# clusterwink_rev0.net
KiCad netlist of a schematic drawn in Altium Designer
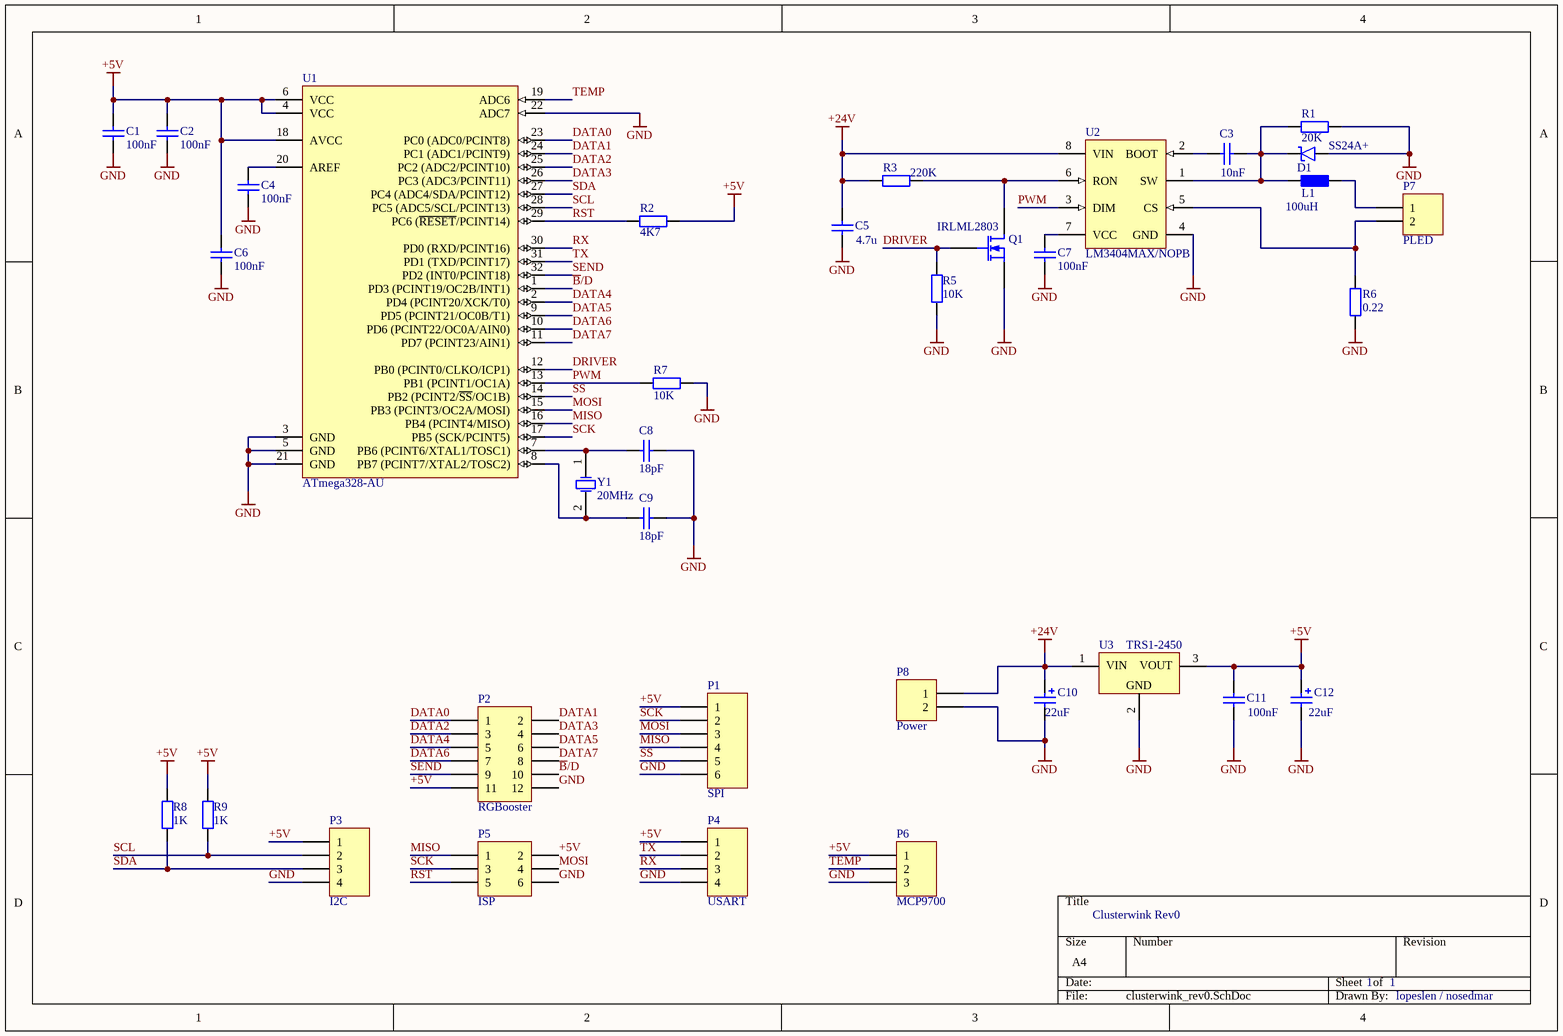
[diagram p0: clusterwink_rev0.SchDoc]

(export (version "E")
  (design (tool "Eeschema 10.0.6"))
  (components
    (comp (ref "C1")
      (value "100nF")
      (footprint "6-0805_M")
      (description "Capacitor")
      (fields (field (name "Comment") "Cap") (field (name "PUBLISHER") "Altium Limited"))
      (libsource (lib "Miscellaneous Devices") (part "Cap"))
    )
    (comp (ref "C2")
      (value "100nF")
      (footprint "6-0805_M")
      (description "Capacitor")
      (fields (field (name "Comment") "Cap") (field (name "PUBLISHER") "Altium Limited"))
      (libsource (lib "Miscellaneous Devices") (part "Cap"))
    )
    (comp (ref "C3")
      (value "10nF")
      (footprint "6-0805_M")
      (description "Capacitor")
      (fields (field (name "Comment") "Cap") (field (name "PUBLISHER") "Altium Limited"))
      (libsource (lib "Miscellaneous Devices") (part "Cap"))
    )
    (comp (ref "C4")
      (value "100nF")
      (footprint "6-0805_M")
      (description "Capacitor")
      (fields (field (name "Comment") "Cap") (field (name "PUBLISHER") "Altium Limited"))
      (libsource (lib "Miscellaneous Devices") (part "Cap"))
    )
    (comp (ref "C5")
      (value "4.7u")
      (footprint "C1206")
      (description "Capacitor")
      (fields (field (name "Comment") "Cap") (field (name "PUBLISHER") "Altium Limited"))
      (libsource (lib "Miscellaneous Devices") (part "Cap"))
    )
    (comp (ref "C6")
      (value "100nF")
      (footprint "6-0805_M")
      (description "Capacitor")
      (fields (field (name "Comment") "Cap") (field (name "PUBLISHER") "Altium Limited"))
      (libsource (lib "Miscellaneous Devices") (part "Cap"))
    )
    (comp (ref "C7")
      (value "100nF")
      (footprint "6-0805_M")
      (description "Capacitor")
      (fields (field (name "Comment") "Cap") (field (name "PUBLISHER") "Altium Limited"))
      (libsource (lib "Miscellaneous Devices") (part "Cap"))
    )
    (comp (ref "C8")
      (value "18pF")
      (footprint "6-0805_M")
      (description "Capacitor")
      (fields (field (name "Comment") "Cap") (field (name "PUBLISHER") "Altium Limited"))
      (libsource (lib "Miscellaneous Devices") (part "Cap"))
    )
    (comp (ref "C9")
      (value "18pF")
      (footprint "6-0805_M")
      (description "Capacitor")
      (fields (field (name "Comment") "Cap") (field (name "PUBLISHER") "Altium Limited"))
      (libsource (lib "Miscellaneous Devices") (part "Cap"))
    )
    (comp (ref "C10")
      (value "22uF")
      (footprint "EEEFK1H220P")
      (description "Polarized Capacitor (Axial)")
      (fields (field (name "Comment") "Cap Pol2") (field (name "PUBLISHER") "Altium Limited"))
      (libsource (lib "Miscellaneous Devices") (part "Cap Pol2"))
    )
    (comp (ref "C11")
      (value "100nF")
      (footprint "6-0805_M")
      (description "Capacitor")
      (fields (field (name "Comment") "Cap") (field (name "PUBLISHER") "Altium Limited"))
      (libsource (lib "Miscellaneous Devices") (part "Cap"))
    )
    (comp (ref "C12")
      (value "22uF")
      (footprint "EEEFK1H220P")
      (description "Polarized Capacitor (Axial)")
      (fields (field (name "Comment") "Cap Pol2") (field (name "PUBLISHER") "Altium Limited"))
      (libsource (lib "Miscellaneous Devices") (part "Cap Pol2"))
    )
    (comp (ref "D1") (value "SS24A+") (footprint "DO-214") (libsource (lib "etp") (part "Schottky")))
    (comp (ref "L1")
      (value "100uH")
      (footprint "ELLCTP")
      (fields (field (name "Comment") "Ind"))
      (libsource (lib "etp") (part "Inductor"))
    )
    (comp (ref "P1")
      (value "SPI")
      (footprint "HDR1X6")
      (description "Header, 6-Pin")
      (fields (field (name "PUBLISHER") "Altium Limited"))
      (libsource (lib "Miscellaneous Connectors") (part "Header 6"))
    )
    (comp (ref "P2")
      (value "RGBooster")
      (footprint "Klemme_90deg_inv")
      (description "Header, 6-Pin, Dual row")
      (fields (field (name "PUBLISHER") "Altium Limited"))
      (libsource (lib "Miscellaneous Connectors") (part "Header 6X2"))
    )
    (comp (ref "P3")
      (value "I2C")
      (footprint "HDR1X4")
      (description "Header, 4-Pin")
      (fields (field (name "PUBLISHER") "Altium Limited"))
      (libsource (lib "Miscellaneous Connectors") (part "Header 4"))
    )
    (comp (ref "P4")
      (value "USART")
      (footprint "HDR1X4")
      (description "Header, 4-Pin")
      (fields (field (name "PUBLISHER") "Altium Limited"))
      (libsource (lib "Miscellaneous Connectors") (part "Header 4"))
    )
    (comp (ref "P5")
      (value "ISP")
      (footprint "AVR_ISP")
      (description "Header, 3-Pin, Dual row")
      (fields (field (name "PUBLISHER") "Altium Limited"))
      (libsource (lib "Miscellaneous Connectors") (part "Header 3X2"))
    )
    (comp (ref "P6")
      (value "MCP9700")
      (footprint "HDR1X3")
      (description "Header, 3-Pin")
      (fields (field (name "PUBLISHER") "Altium Limited"))
      (libsource (lib "Miscellaneous Connectors") (part "Header 3"))
    )
    (comp (ref "P7")
      (value "PLED")
      (footprint "HDR1X2")
      (description "Header, 2-Pin")
      (fields (field (name "PUBLISHER") "Altium Limited"))
      (libsource (lib "") (part "Header 2_1"))
    )
    (comp (ref "P8")
      (value "Power")
      (footprint "HDR1X2")
      (description "Header, 2-Pin")
      (fields (field (name "PUBLISHER") "Altium Limited"))
      (libsource (lib "Miscellaneous Connectors") (part "Header 2"))
    )
    (comp (ref "Q1")
      (value "IRLML2803")
      (footprint "SOT-23")
      (description "N-Channel MOSFET")
      (fields (field (name "PUBLISHER") "Altium Limited"))
      (libsource (lib "Miscellaneous Devices") (part "MOSFET-N"))
    )
    (comp (ref "R1")
      (value "20K")
      (footprint "6-0805_M")
      (description "Resistor")
      (fields (field (name "Comment") "Res2") (field (name "PUBLISHER") "Altium Limited"))
      (libsource (lib "") (part "Res2_2"))
    )
    (comp (ref "R2")
      (value "4K7")
      (footprint "6-0805_M")
      (description "Resistor")
      (fields (field (name "Comment") "Res2") (field (name "PUBLISHER") "Altium Limited"))
      (libsource (lib "") (part "Res2_2"))
    )
    (comp (ref "R3")
      (value "220K")
      (footprint "6-0805_M")
      (description "Resistor")
      (fields (field (name "Comment") "Res2") (field (name "PUBLISHER") "Altium Limited"))
      (libsource (lib "") (part "Res2_3"))
    )
    (comp (ref "R5")
      (value "10K")
      (footprint "6-0805_M")
      (description "Resistor")
      (fields (field (name "Comment") "Res2") (field (name "PUBLISHER") "Altium Limited"))
      (libsource (lib "Miscellaneous Devices") (part "Res2"))
    )
    (comp (ref "R6")
      (value "0.22")
      (footprint "C1206")
      (description "Resistor")
      (fields (field (name "Comment") "Res2") (field (name "PUBLISHER") "Altium Limited"))
      (libsource (lib "Miscellaneous Devices") (part "Res2"))
    )
    (comp (ref "R7")
      (value "10K")
      (footprint "6-0805_M")
      (description "Resistor")
      (fields (field (name "Comment") "Res2") (field (name "PUBLISHER") "Altium Limited"))
      (libsource (lib "") (part "Res2_2"))
    )
    (comp (ref "R8")
      (value "1K")
      (footprint "6-0805_M")
      (description "Resistor")
      (fields (field (name "Comment") "Res2") (field (name "PUBLISHER") "Altium Limited"))
      (libsource (lib "") (part "Res2_1"))
    )
    (comp (ref "R9")
      (value "1K")
      (footprint "6-0805_M")
      (description "Resistor")
      (fields (field (name "Comment") "Res2") (field (name "PUBLISHER") "Altium Limited"))
      (libsource (lib "") (part "Res2_1"))
    )
    (comp (ref "U1")
      (value "ATmega328-AU")
      (footprint "32A_N")
      (libsource (lib "Atmel Microcontroller megaAVR") (part "ATmega328-AU"))
    )
    (comp (ref "U2")
      (value "LM3404MAX/NOPB")
      (footprint "M08A_N")
      (description "1.0A Constant Current Buck Regulator for High Power LED Drivers, 8-pin Narrow SOIC, Pb-Free")
      (fields (field (name "MANUFACTURER") "National Semiconductor"))
      (libsource (lib "National Semiconductor MiscPower") (part "LM3404MAX/NOPB"))
    )
    (comp (ref "U3") (value "TRS1-2450") (footprint "TRS 1-2450") (libsource (lib "etp") (part "TSR1-2450")))
    (comp (ref "Y1")
      (value "20MHz")
      (footprint "CRYSTAL")
      (description "Crystal Oscillator")
      (fields (field (name "PUBLISHER") "Altium Limited"))
      (libsource (lib "Miscellaneous Devices") (part "XTAL"))
    )
  )
  (nets
    (net (code "1") (name "+5V") (class "Default")
      (node (ref "C1") (pin "2") (pinfunction "2_2") (pintype "passive"))
      (node (ref "C11") (pin "2") (pinfunction "2_2") (pintype "passive"))
      (node (ref "C12") (pin "1") (pinfunction "1_1") (pintype "passive"))
      (node (ref "C2") (pin "2") (pinfunction "2_2") (pintype "passive"))
      (node (ref "C6") (pin "2") (pinfunction "2_2") (pintype "passive"))
      (node (ref "P1") (pin "1") (pinfunction "1_1") (pintype "passive"))
      (node (ref "P2") (pin "11") (pinfunction "11_11") (pintype "passive"))
      (node (ref "P3") (pin "1") (pinfunction "1_1") (pintype "passive"))
      (node (ref "P4") (pin "1") (pinfunction "1_1") (pintype "passive"))
      (node (ref "P5") (pin "2") (pinfunction "2_2") (pintype "passive"))
      (node (ref "P6") (pin "1") (pinfunction "1_1") (pintype "passive"))
      (node (ref "R2") (pin "1") (pinfunction "1_1") (pintype "passive"))
      (node (ref "R8") (pin "1") (pinfunction "1_1") (pintype "passive"))
      (node (ref "R9") (pin "1") (pinfunction "1_1") (pintype "passive"))
      (node (ref "U1") (pin "18") (pinfunction "AVCC_18") (pintype "power_in"))
      (node (ref "U1") (pin "4") (pinfunction "VCC_4") (pintype "power_in"))
      (node (ref "U1") (pin "6") (pinfunction "VCC_6") (pintype "power_in"))
      (node (ref "U3") (pin "3") (pinfunction "+VOUT_3") (pintype "passive"))
    )
    (net (code "2") (name "+24V") (class "Default")
      (node (ref "C10") (pin "1") (pinfunction "1_1") (pintype "passive"))
      (node (ref "C5") (pin "2") (pinfunction "2_2") (pintype "passive"))
      (node (ref "P8") (pin "1") (pinfunction "1_1") (pintype "passive"))
      (node (ref "R3") (pin "1") (pinfunction "1_1") (pintype "passive"))
      (node (ref "U2") (pin "8") (pinfunction "VIN_8") (pintype "power_in"))
      (node (ref "U3") (pin "1") (pinfunction "+VIN_1") (pintype "passive"))
    )
    (net (code "3") (name "/DATA0") (class "Default")
      (node (ref "P2") (pin "1") (pinfunction "1_1") (pintype "passive"))
      (node (ref "U1") (pin "23") (pinfunction "PC0_(ADC0/PCINT8)_23") (pintype "bidirectional"))
    )
    (net (code "4") (name "/DATA1") (class "Default")
      (node (ref "P2") (pin "2") (pinfunction "2_2") (pintype "passive"))
      (node (ref "U1") (pin "24") (pinfunction "PC1_(ADC1/PCINT9)_24") (pintype "bidirectional"))
    )
    (net (code "5") (name "/DATA2") (class "Default")
      (node (ref "P2") (pin "3") (pinfunction "3_3") (pintype "passive"))
      (node (ref "U1") (pin "25") (pinfunction "PC2_(ADC2/PCINT10)_25") (pintype "bidirectional"))
    )
    (net (code "6") (name "/DATA3") (class "Default")
      (node (ref "P2") (pin "4") (pinfunction "4_4") (pintype "passive"))
      (node (ref "U1") (pin "26") (pinfunction "PC3_(ADC3/PCINT11)_26") (pintype "bidirectional"))
    )
    (net (code "7") (name "/DATA4") (class "Default")
      (node (ref "P2") (pin "5") (pinfunction "5_5") (pintype "passive"))
      (node (ref "U1") (pin "2") (pinfunction "PD4_(PCINT20/XCK/T0)_2") (pintype "bidirectional"))
    )
    (net (code "8") (name "/DATA5") (class "Default")
      (node (ref "P2") (pin "6") (pinfunction "6_6") (pintype "passive"))
      (node (ref "U1") (pin "9") (pinfunction "PD5_(PCINT21/OC0B/T1)_9") (pintype "bidirectional"))
    )
    (net (code "9") (name "/DATA6") (class "Default")
      (node (ref "P2") (pin "7") (pinfunction "7_7") (pintype "passive"))
      (node (ref "U1") (pin "10") (pinfunction "PD6_(PCINT22/OC0A/AIN0)_10") (pintype "bidirectional"))
    )
    (net (code "10") (name "/DATA7") (class "Default")
      (node (ref "P2") (pin "8") (pinfunction "8_8") (pintype "passive"))
      (node (ref "U1") (pin "11") (pinfunction "PD7_(PCINT23/AIN1)_11") (pintype "bidirectional"))
    )
    (net (code "11") (name "/DRIVER") (class "Default")
      (node (ref "Q1") (pin "2") (pinfunction "G_2") (pintype "passive"))
      (node (ref "R5") (pin "2") (pinfunction "2_2") (pintype "passive"))
      (node (ref "U1") (pin "12") (pinfunction "PB0_(PCINT0/CLKO/ICP1)_12") (pintype "bidirectional"))
    )
    (net (code "12") (name "/MISO") (class "Default")
      (node (ref "P1") (pin "4") (pinfunction "4_4") (pintype "passive"))
      (node (ref "P5") (pin "1") (pinfunction "1_1") (pintype "passive"))
      (node (ref "U1") (pin "16") (pinfunction "PB4_(PCINT4/MISO)_16") (pintype "bidirectional"))
    )
    (net (code "13") (name "/MOSI") (class "Default")
      (node (ref "P1") (pin "3") (pinfunction "3_3") (pintype "passive"))
      (node (ref "P5") (pin "4") (pinfunction "4_4") (pintype "passive"))
      (node (ref "U1") (pin "15") (pinfunction "PB3_(PCINT3/OC2A/MOSI)_15") (pintype "bidirectional"))
    )
    (net (code "14") (name "/PWM") (class "Default")
      (node (ref "R7") (pin "2") (pinfunction "2_2") (pintype "passive"))
      (node (ref "U1") (pin "13") (pinfunction "PB1_(PCINT1/OC1A)_13") (pintype "bidirectional"))
      (node (ref "U2") (pin "3") (pinfunction "DIM_3") (pintype "input"))
    )
    (net (code "15") (name "/RST") (class "Default")
      (node (ref "P5") (pin "5") (pinfunction "5_5") (pintype "passive"))
      (node (ref "R2") (pin "2") (pinfunction "2_2") (pintype "passive"))
      (node (ref "U1") (pin "29") (pinfunction "PC6_(~{RESET}/PCINT14)_29") (pintype "bidirectional"))
    )
    (net (code "16") (name "/RX") (class "Default")
      (node (ref "P4") (pin "3") (pinfunction "3_3") (pintype "passive"))
      (node (ref "U1") (pin "30") (pinfunction "PD0_(RXD/PCINT16)_30") (pintype "bidirectional"))
    )
    (net (code "17") (name "/SCK") (class "Default")
      (node (ref "P1") (pin "2") (pinfunction "2_2") (pintype "passive"))
      (node (ref "P5") (pin "3") (pinfunction "3_3") (pintype "passive"))
      (node (ref "U1") (pin "17") (pinfunction "PB5_(SCK/PCINT5)_17") (pintype "bidirectional"))
    )
    (net (code "18") (name "/SCL") (class "Default")
      (node (ref "P3") (pin "2") (pinfunction "2_2") (pintype "passive"))
      (node (ref "R9") (pin "2") (pinfunction "2_2") (pintype "passive"))
      (node (ref "U1") (pin "28") (pinfunction "PC5_(ADC5/SCL/PCINT13)_28") (pintype "bidirectional"))
    )
    (net (code "19") (name "/SDA") (class "Default")
      (node (ref "P3") (pin "3") (pinfunction "3_3") (pintype "passive"))
      (node (ref "R8") (pin "2") (pinfunction "2_2") (pintype "passive"))
      (node (ref "U1") (pin "27") (pinfunction "PC4_(ADC4/SDA/PCINT12)_27") (pintype "bidirectional"))
    )
    (net (code "20") (name "/SEND") (class "Default")
      (node (ref "P2") (pin "9") (pinfunction "9_9") (pintype "passive"))
      (node (ref "U1") (pin "32") (pinfunction "PD2_(INT0/PCINT18)_32") (pintype "bidirectional"))
    )
    (net (code "21") (name "/TEMP") (class "Default")
      (node (ref "P6") (pin "2") (pinfunction "2_2") (pintype "passive"))
      (node (ref "U1") (pin "19") (pinfunction "ADC6_19") (pintype "input"))
    )
    (net (code "22") (name "/TX") (class "Default")
      (node (ref "P4") (pin "2") (pinfunction "2_2") (pintype "passive"))
      (node (ref "U1") (pin "31") (pinfunction "PD1_(TXD/PCINT17)_31") (pintype "bidirectional"))
    )
    (net (code "23") (name "/~{B}{slash}D") (class "Default")
      (node (ref "P2") (pin "10") (pinfunction "10_10") (pintype "passive"))
      (node (ref "U1") (pin "1") (pinfunction "PD3_(PCINT19/OC2B/INT1)_1") (pintype "bidirectional"))
    )
    (net (code "24") (name "/~{SS}") (class "Default")
      (node (ref "P1") (pin "5") (pinfunction "5_5") (pintype "passive"))
      (node (ref "U1") (pin "14") (pinfunction "PB2_(PCINT2/~{SS}/OC1B)_14") (pintype "bidirectional"))
    )
    (net (code "25") (name "GND") (class "Default")
      (node (ref "C1") (pin "1") (pinfunction "1_1") (pintype "passive"))
      (node (ref "C10") (pin "2") (pinfunction "2_2") (pintype "passive"))
      (node (ref "C11") (pin "1") (pinfunction "1_1") (pintype "passive"))
      (node (ref "C12") (pin "2") (pinfunction "2_2") (pintype "passive"))
      (node (ref "C2") (pin "1") (pinfunction "1_1") (pintype "passive"))
      (node (ref "C4") (pin "1") (pinfunction "1_1") (pintype "passive"))
      (node (ref "C5") (pin "1") (pinfunction "1_1") (pintype "passive"))
      (node (ref "C6") (pin "1") (pinfunction "1_1") (pintype "passive"))
      (node (ref "C7") (pin "1") (pinfunction "1_1") (pintype "passive"))
      (node (ref "C8") (pin "1") (pinfunction "1_1") (pintype "passive"))
      (node (ref "C9") (pin "1") (pinfunction "1_1") (pintype "passive"))
      (node (ref "D1") (pin "1") (pinfunction "A_1") (pintype "passive"))
      (node (ref "P1") (pin "6") (pinfunction "6_6") (pintype "passive"))
      (node (ref "P2") (pin "12") (pinfunction "12_12") (pintype "passive"))
      (node (ref "P3") (pin "4") (pinfunction "4_4") (pintype "passive"))
      (node (ref "P4") (pin "4") (pinfunction "4_4") (pintype "passive"))
      (node (ref "P5") (pin "6") (pinfunction "6_6") (pintype "passive"))
      (node (ref "P6") (pin "3") (pinfunction "3_3") (pintype "passive"))
      (node (ref "P8") (pin "2") (pinfunction "2_2") (pintype "passive"))
      (node (ref "Q1") (pin "3") (pinfunction "S_3") (pintype "passive"))
      (node (ref "R1") (pin "1") (pinfunction "1_1") (pintype "passive"))
      (node (ref "R5") (pin "1") (pinfunction "1_1") (pintype "passive"))
      (node (ref "R6") (pin "1") (pinfunction "1_1") (pintype "passive"))
      (node (ref "R7") (pin "1") (pinfunction "1_1") (pintype "passive"))
      (node (ref "U1") (pin "21") (pinfunction "GND_21") (pintype "power_in"))
      (node (ref "U1") (pin "22") (pinfunction "ADC7_22") (pintype "input"))
      (node (ref "U1") (pin "3") (pinfunction "GND_3") (pintype "power_in"))
      (node (ref "U1") (pin "5") (pinfunction "GND_5") (pintype "power_in"))
      (node (ref "U2") (pin "4") (pinfunction "GND_4") (pintype "power_in"))
      (node (ref "U3") (pin "2") (pinfunction "GND_2") (pintype "passive"))
    )
    (net (code "26") (name "Net-(D1-K)") (class "Default")
      (node (ref "C3") (pin "2") (pinfunction "2_2") (pintype "passive"))
      (node (ref "D1") (pin "2") (pinfunction "K_2") (pintype "passive"))
      (node (ref "L1") (pin "1") (pinfunction "1_1") (pintype "passive"))
      (node (ref "R1") (pin "2") (pinfunction "2_2") (pintype "passive"))
      (node (ref "U2") (pin "1") (pinfunction "SW_1") (pintype "power_in"))
    )
    (net (code "27") (name "Net-(L1-Pad2)") (class "Default")
      (node (ref "L1") (pin "2") (pinfunction "2_2") (pintype "passive"))
      (node (ref "P7") (pin "1") (pinfunction "1_1") (pintype "passive"))
    )
    (net (code "28") (name "Net-(Q1-D)") (class "Default")
      (node (ref "Q1") (pin "1") (pinfunction "D_1") (pintype "passive"))
      (node (ref "R3") (pin "2") (pinfunction "2_2") (pintype "passive"))
      (node (ref "U2") (pin "6") (pinfunction "RON_6") (pintype "input"))
    )
    (net (code "29") (name "Net-(U1-AREF)") (class "Default")
      (node (ref "C4") (pin "2") (pinfunction "2_2") (pintype "passive"))
      (node (ref "U1") (pin "20") (pinfunction "AREF_20") (pintype "passive"))
    )
    (net (code "30") (name "Net-(U1-PB6_(PCINT6{slash}XTAL1{slash}TOSC1))") (class "Default")
      (node (ref "C8") (pin "2") (pinfunction "2_2") (pintype "passive"))
      (node (ref "U1") (pin "7") (pinfunction "PB6_(PCINT6/XTAL1/TOSC1)_7") (pintype "bidirectional"))
      (node (ref "Y1") (pin "1") (pinfunction "OSC1_1") (pintype "passive"))
    )
    (net (code "31") (name "Net-(U1-PB7_(PCINT7{slash}XTAL2{slash}TOSC2))") (class "Default")
      (node (ref "C9") (pin "2") (pinfunction "2_2") (pintype "passive"))
      (node (ref "U1") (pin "8") (pinfunction "PB7_(PCINT7/XTAL2/TOSC2)_8") (pintype "bidirectional"))
      (node (ref "Y1") (pin "2") (pinfunction "OSC2_2") (pintype "passive"))
    )
    (net (code "32") (name "Net-(U2-BOOT)") (class "Default")
      (node (ref "C3") (pin "1") (pinfunction "1_1") (pintype "passive"))
      (node (ref "U2") (pin "2") (pinfunction "BOOT_2") (pintype "input"))
    )
    (net (code "33") (name "Net-(U2-CS)") (class "Default")
      (node (ref "P7") (pin "2") (pinfunction "2_2") (pintype "passive"))
      (node (ref "R6") (pin "2") (pinfunction "2_2") (pintype "passive"))
      (node (ref "U2") (pin "5") (pinfunction "CS_5") (pintype "input"))
    )
    (net (code "34") (name "Net-(U2-VCC)") (class "Default")
      (node (ref "C7") (pin "2") (pinfunction "2_2") (pintype "passive"))
      (node (ref "U2") (pin "7") (pinfunction "VCC_7") (pintype "power_in"))
    )
  )
)
